# ESP12_DEV_00.net
KiCad netlist of a schematic drawn in Altium Designer
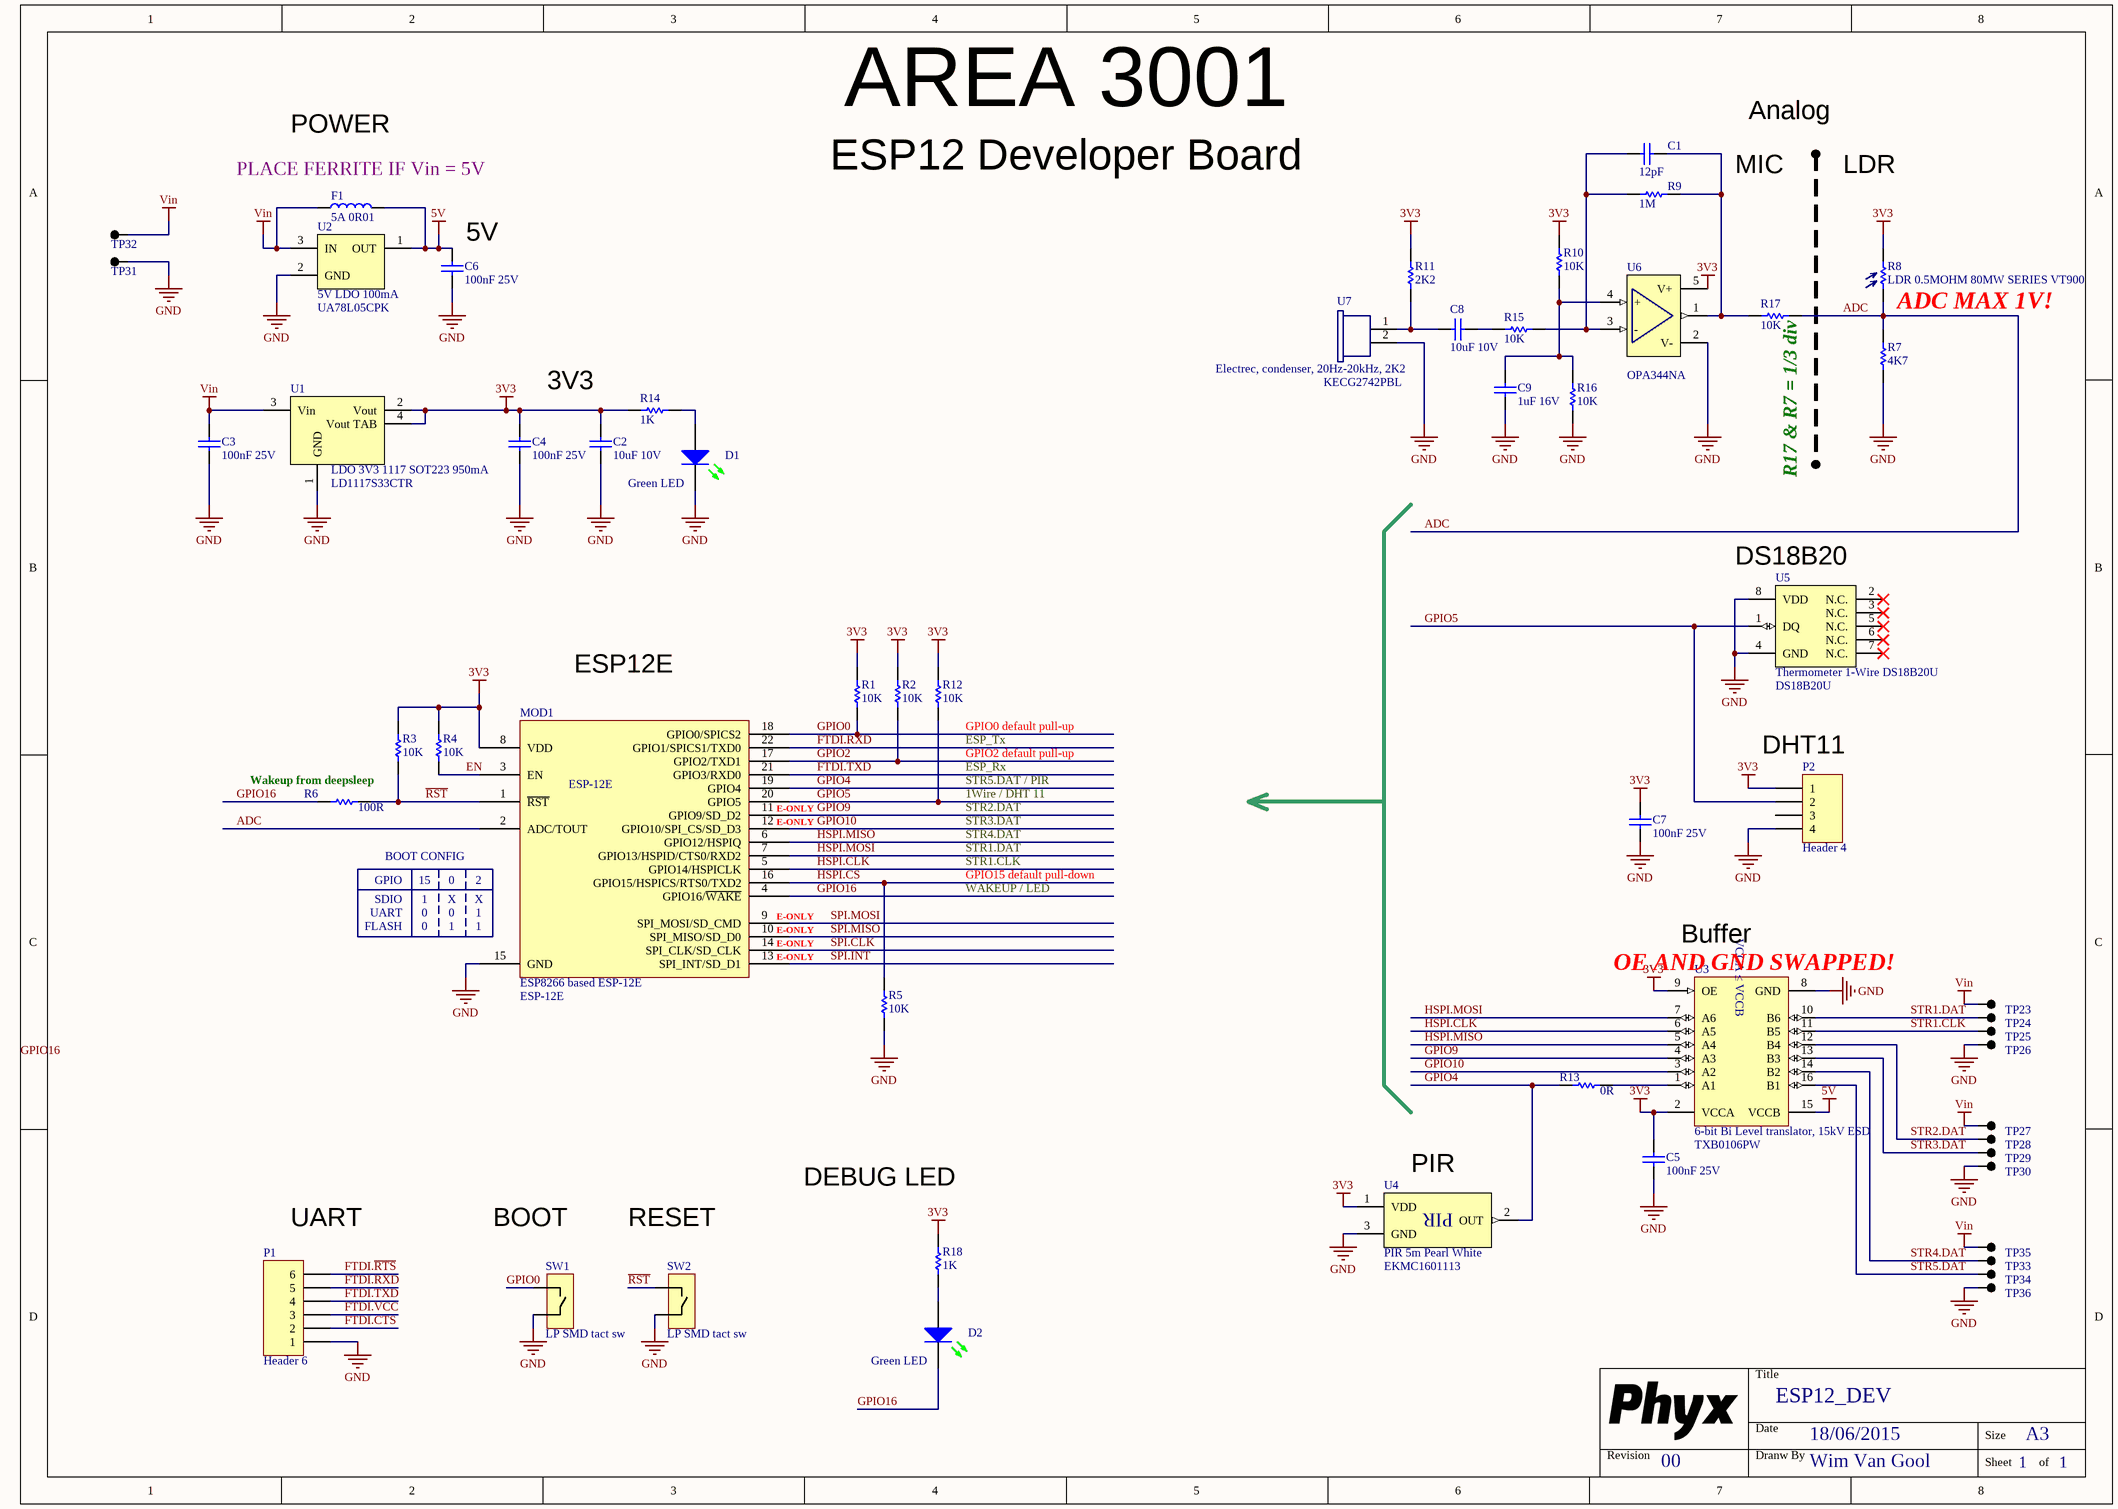
[diagram p0: ESP12_DEV_00.SchDoc]

(export (version "E")
  (design (tool "Eeschema 10.0.6"))
  (components
    (comp (ref "C1")
      (value "12pF")
      (footprint "C0603")
      (description "Capacitor Ceramic")
      (fields (field (name "Comment") "CAP_CERAMIC"))
      (libsource (lib "Phyx_Components") (part "CAP_CERAMIC"))
    )
    (comp (ref "C2")
      (value "10uF 10V")
      (footprint "C0805")
      (description "Capacitor Ceramic")
      (fields (field (name "Comment") "CAP_CERAMIC"))
      (libsource (lib "Phyx_Components") (part "CAP_CERAMIC"))
    )
    (comp (ref "C3")
      (value "100nF 25V")
      (footprint "C0805")
      (description "Capacitor Ceramic")
      (fields (field (name "Comment") "CAP_CERAMIC"))
      (libsource (lib "Phyx_Components") (part "CAP_CERAMIC"))
    )
    (comp (ref "C4")
      (value "100nF 25V")
      (footprint "C0805")
      (description "Capacitor Ceramic")
      (fields (field (name "Comment") "CAP_CERAMIC"))
      (libsource (lib "Phyx_Components") (part "CAP_CERAMIC"))
    )
    (comp (ref "C5")
      (value "100nF 25V")
      (footprint "C0805")
      (description "Capacitor Ceramic")
      (fields (field (name "Comment") "CAP_CERAMIC"))
      (libsource (lib "Phyx_Components") (part "CAP_CERAMIC"))
    )
    (comp (ref "C6")
      (value "100nF 25V")
      (footprint "C0805")
      (description "Capacitor Ceramic")
      (fields (field (name "Comment") "CAP_CERAMIC"))
      (libsource (lib "Phyx_Components") (part "CAP_CERAMIC"))
    )
    (comp (ref "C7")
      (value "100nF 25V")
      (footprint "C0805")
      (description "Capacitor Ceramic")
      (fields (field (name "Comment") "CAP_CERAMIC"))
      (libsource (lib "Phyx_Components") (part "CAP_CERAMIC"))
    )
    (comp (ref "C8")
      (value "10uF 10V")
      (footprint "C0805")
      (description "Capacitor Ceramic")
      (fields (field (name "Comment") "CAP_CERAMIC"))
      (libsource (lib "Phyx_Components") (part "CAP_CERAMIC"))
    )
    (comp (ref "C9")
      (value "1uF 16V")
      (footprint "C0603")
      (description "Capacitor Ceramic")
      (fields (field (name "Comment") "CAP_CERAMIC"))
      (libsource (lib "Phyx_Components") (part "CAP_CERAMIC"))
    )
    (comp (ref "D1")
      (value "Green LED")
      (footprint "LED_0805_GR")
      (description "=Description")
      (libsource (lib "Phyx_Components") (part "LED_GREEN"))
    )
    (comp (ref "D2")
      (value "Green LED")
      (footprint "LED_0805_GR")
      (description "=Description")
      (libsource (lib "Phyx_Components") (part "LED_GREEN"))
    )
    (comp (ref "F1")
      (value "5A 0R01")
      (footprint "L0805")
      (fields (field (name "Comment") "FERRITE"))
      (libsource (lib "Phyx_Components") (part "FERRITE"))
    )
    (comp (ref "MOD1")
      (value "ESP8266 based ESP-12E")
      (footprint "ESP-12E")
      (description "=Description")
      (fields (field (name "ALTIUM_VALUE") "ESP-12E"))
      (libsource (lib "Phyx_Components") (part "ESP-12E"))
    )
    (comp (ref "P1")
      (value "Header 6")
      (footprint "HDR1X6")
      (libsource (lib "Phyx_Components") (part "Header 6"))
    )
    (comp (ref "P2")
      (value "Header 4")
      (footprint "HDR1X4")
      (libsource (lib "Phyx_Components") (part "Header 4"))
    )
    (comp (ref "R1")
      (value "10K")
      (footprint "R0603")
      (fields (field (name "Comment") "RESISTOR"))
      (libsource (lib "Phyx_Components") (part "RESISTOR"))
    )
    (comp (ref "R2")
      (value "10K")
      (footprint "R0603")
      (fields (field (name "Comment") "RESISTOR"))
      (libsource (lib "Phyx_Components") (part "RESISTOR"))
    )
    (comp (ref "R3")
      (value "10K")
      (footprint "R0603")
      (fields (field (name "Comment") "RESISTOR"))
      (libsource (lib "Phyx_Components") (part "RESISTOR"))
    )
    (comp (ref "R4")
      (value "10K")
      (footprint "R0603")
      (fields (field (name "Comment") "RESISTOR"))
      (libsource (lib "Phyx_Components") (part "RESISTOR"))
    )
    (comp (ref "R5")
      (value "10K")
      (footprint "R0603")
      (fields (field (name "Comment") "RESISTOR"))
      (libsource (lib "Phyx_Components") (part "RESISTOR"))
    )
    (comp (ref "R6")
      (value "100R")
      (footprint "R0603")
      (fields (field (name "Comment") "RESISTOR"))
      (libsource (lib "Phyx_Components") (part "RESISTOR"))
    )
    (comp (ref "R7")
      (value "4K7")
      (footprint "R0603")
      (fields (field (name "Comment") "RESISTOR"))
      (libsource (lib "Phyx_Components") (part "RESISTOR"))
    )
    (comp (ref "R8")
      (value "LDR 0.5MOHM 80MW SERIES VT900")
      (footprint "VT900")
      (description "=Description")
      (libsource (lib "Phyx_Components") (part "LDR_2"))
    )
    (comp (ref "R9")
      (value "1M")
      (footprint "R0603")
      (fields (field (name "Comment") "RESISTOR"))
      (libsource (lib "Phyx_Components") (part "RESISTOR"))
    )
    (comp (ref "R10")
      (value "10K")
      (footprint "R0603")
      (fields (field (name "Comment") "RESISTOR"))
      (libsource (lib "Phyx_Components") (part "RESISTOR"))
    )
    (comp (ref "R11")
      (value "2K2")
      (footprint "R0603")
      (fields (field (name "Comment") "RESISTOR"))
      (libsource (lib "Phyx_Components") (part "RESISTOR"))
    )
    (comp (ref "R12")
      (value "10K")
      (footprint "R0603")
      (fields (field (name "Comment") "RESISTOR"))
      (libsource (lib "Phyx_Components") (part "RESISTOR"))
    )
    (comp (ref "R13")
      (value "0R")
      (footprint "R0603")
      (fields (field (name "Comment") "RESISTOR"))
      (libsource (lib "Phyx_Components") (part "RESISTOR"))
    )
    (comp (ref "R14")
      (value "1K")
      (footprint "R0603")
      (fields (field (name "Comment") "RESISTOR"))
      (libsource (lib "Phyx_Components") (part "RESISTOR"))
    )
    (comp (ref "R15")
      (value "10K")
      (footprint "R0603")
      (fields (field (name "Comment") "RESISTOR"))
      (libsource (lib "Phyx_Components") (part "RESISTOR"))
    )
    (comp (ref "R16")
      (value "10K")
      (footprint "R0603")
      (fields (field (name "Comment") "RESISTOR"))
      (libsource (lib "Phyx_Components") (part "RESISTOR"))
    )
    (comp (ref "R17")
      (value "10K")
      (footprint "R0603")
      (fields (field (name "Comment") "RESISTOR"))
      (libsource (lib "Phyx_Components") (part "RESISTOR"))
    )
    (comp (ref "R18")
      (value "1K")
      (footprint "R0603")
      (fields (field (name "Comment") "RESISTOR"))
      (libsource (lib "Phyx_Components") (part "RESISTOR"))
    )
    (comp (ref "SW1")
      (value "LP SMD tact sw")
      (footprint "CK_KMR4")
      (libsource (lib "Phyx_Components") (part "SW_TACT"))
    )
    (comp (ref "SW2")
      (value "LP SMD tact sw")
      (footprint "CK_KMR4")
      (libsource (lib "Phyx_Components") (part "SW_TACT"))
    )
    (comp (ref "TP23")
      (value "TEST_PAD")
      (footprint "TP_2x3mm")
      (libsource (lib "Phyx_Components") (part "TEST_PAD"))
    )
    (comp (ref "TP24")
      (value "TEST_PAD")
      (footprint "TP_2x3mm")
      (libsource (lib "Phyx_Components") (part "TEST_PAD"))
    )
    (comp (ref "TP25")
      (value "TEST_PAD")
      (footprint "TP_2x3mm")
      (libsource (lib "Phyx_Components") (part "TEST_PAD"))
    )
    (comp (ref "TP26")
      (value "TEST_PAD")
      (footprint "TP_2x3mm")
      (libsource (lib "Phyx_Components") (part "TEST_PAD"))
    )
    (comp (ref "TP27")
      (value "TEST_PAD")
      (footprint "TP_2x3mm")
      (libsource (lib "Phyx_Components") (part "TEST_PAD"))
    )
    (comp (ref "TP28")
      (value "TEST_PAD")
      (footprint "TP_2x3mm")
      (libsource (lib "Phyx_Components") (part "TEST_PAD"))
    )
    (comp (ref "TP29")
      (value "TEST_PAD")
      (footprint "TP_2x3mm")
      (libsource (lib "Phyx_Components") (part "TEST_PAD"))
    )
    (comp (ref "TP30")
      (value "TEST_PAD")
      (footprint "TP_2x3mm")
      (libsource (lib "Phyx_Components") (part "TEST_PAD"))
    )
    (comp (ref "TP31")
      (value "TEST_PAD")
      (footprint "TP_2x3mm")
      (libsource (lib "Phyx_Components") (part "TEST_PAD"))
    )
    (comp (ref "TP32")
      (value "TEST_PAD")
      (footprint "TP_2x3mm")
      (libsource (lib "Phyx_Components") (part "TEST_PAD"))
    )
    (comp (ref "TP33")
      (value "TEST_PAD")
      (footprint "TP_2x3mm")
      (libsource (lib "Phyx_Components") (part "TEST_PAD"))
    )
    (comp (ref "TP34")
      (value "TEST_PAD")
      (footprint "TP_2x3mm")
      (libsource (lib "Phyx_Components") (part "TEST_PAD"))
    )
    (comp (ref "TP35")
      (value "TEST_PAD")
      (footprint "TP_2x3mm")
      (libsource (lib "Phyx_Components") (part "TEST_PAD"))
    )
    (comp (ref "TP36")
      (value "TEST_PAD")
      (footprint "TP_2x3mm")
      (libsource (lib "Phyx_Components") (part "TEST_PAD"))
    )
    (comp (ref "U1")
      (value "LDO 3V3 1117 SOT223 950mA")
      (footprint "SOT223")
      (description "=Designator")
      (fields (field (name "ALTIUM_VALUE") "LD1117S33CTR"))
      (libsource (lib "Phyx_Components") (part "LDO_1117_SOT223"))
    )
    (comp (ref "U2")
      (value "5V LDO 100mA")
      (footprint "TI_PK")
      (description "LDO 5V 100mA")
      (fields (field (name "ALTIUM_VALUE") "UA78L05CPK"))
      (libsource (lib "Phyx_Components") (part "UA78L05CPK"))
    )
    (comp (ref "U3")
      (value "6-bit Bi Level translator, 15kV ESD")
      (footprint "TI_PW_R-PDSO-G16")
      (description "=Description")
      (fields (field (name "ALTIUM_VALUE") "TXB0106PW"))
      (libsource (lib "Phyx_Components") (part "TXB0106PW"))
    )
    (comp (ref "U4")
      (value "PIR 5m Pearl White")
      (footprint "PAN_EKMC1601113")
      (description "=Description")
      (fields (field (name "ALTIUM_VALUE") "EKMC1601113"))
      (libsource (lib "Phyx_Components") (part "EKMC160x111x"))
    )
    (comp (ref "U5")
      (value "Thermometer 1-Wire DS18B20U")
      (footprint "MAX_uSOP8")
      (description "=Description")
      (fields (field (name "ALTIUM_VALUE") "DS18B20U"))
      (libsource (lib "Phyx_Components") (part "DS18B20U"))
    )
    (comp (ref "U6")
      (value "OPA344NA")
      (footprint "TI_DBV_R-PDSO-G5")
      (description "=Description")
      (fields (field (name "Comment") "Low Power, Single supply, Rail-to-Rail opamp"))
      (libsource (lib "Phyx_Components") (part "OPA34xNA"))
    )
    (comp (ref "U7")
      (value "Electrec, condenser, 20Hz-20kHz, 2K2")
      (footprint "MIC_2742PB")
      (description "=Description")
      (fields (field (name "ALTIUM_VALUE") "KECG2742PBL"))
      (libsource (lib "Phyx_Components") (part "MIC_ELEC_2"))
    )
  )
  (nets
    (net (code "1") (name "/ADC") (class "Default")
      (node (ref "MOD1") (pin "2") (pinfunction "ADC/TOUT_2") (pintype "passive"))
      (node (ref "R17") (pin "1") (pinfunction "1_1") (pintype "passive"))
      (node (ref "R7") (pin "1") (pinfunction "1_1") (pintype "passive"))
      (node (ref "R8") (pin "2") (pinfunction "2_2") (pintype "passive"))
    )
    (net (code "2") (name "/EN") (class "Default")
      (node (ref "MOD1") (pin "3") (pinfunction "EN_3") (pintype "passive"))
      (node (ref "R4") (pin "2") (pinfunction "2_2") (pintype "passive"))
    )
    (net (code "3") (name "/FTDI.RXD") (class "Default")
      (node (ref "MOD1") (pin "22") (pinfunction "GPIO1/SPICS1/TXD0_22") (pintype "passive"))
      (node (ref "P1") (pin "5") (pinfunction "5_5") (pintype "passive"))
    )
    (net (code "4") (name "/FTDI.TXD") (class "Default")
      (node (ref "MOD1") (pin "21") (pinfunction "GPIO3/RXD0_21") (pintype "passive"))
      (node (ref "P1") (pin "4") (pinfunction "4_4") (pintype "passive"))
    )
    (net (code "5") (name "/FTDI.VCC") (class "Default")
      (node (ref "P1") (pin "3") (pinfunction "3_3") (pintype "passive"))
    )
    (net (code "6") (name "/FTDI.~{CTS}") (class "Default")
      (node (ref "P1") (pin "2") (pinfunction "2_2") (pintype "passive"))
    )
    (net (code "7") (name "/FTDI.~{RTS}") (class "Default")
      (node (ref "P1") (pin "6") (pinfunction "6_6") (pintype "passive"))
    )
    (net (code "8") (name "/GPIO0") (class "Default")
      (node (ref "MOD1") (pin "18") (pinfunction "GPIO0/SPICS2_18") (pintype "passive"))
      (node (ref "R1") (pin "2") (pinfunction "2_2") (pintype "passive"))
      (node (ref "SW1") (pin "1") (pinfunction "1_1") (pintype "passive"))
    )
    (net (code "9") (name "/GPIO2") (class "Default")
      (node (ref "MOD1") (pin "17") (pinfunction "GPIO2/TXD1_17") (pintype "passive"))
      (node (ref "R2") (pin "2") (pinfunction "2_2") (pintype "passive"))
    )
    (net (code "10") (name "/GPIO4") (class "Default")
      (node (ref "MOD1") (pin "19") (pinfunction "GPIO4_19") (pintype "passive"))
      (node (ref "R13") (pin "2") (pinfunction "2_2") (pintype "passive"))
      (node (ref "U4") (pin "2") (pinfunction "OUT_2") (pintype "output"))
    )
    (net (code "11") (name "/GPIO5") (class "Default")
      (node (ref "MOD1") (pin "20") (pinfunction "GPIO5_20") (pintype "passive"))
      (node (ref "P2") (pin "2") (pinfunction "2_2") (pintype "passive"))
      (node (ref "R12") (pin "2") (pinfunction "2_2") (pintype "passive"))
      (node (ref "U5") (pin "1") (pinfunction "DQ_1") (pintype "bidirectional"))
    )
    (net (code "12") (name "/GPIO9") (class "Default")
      (node (ref "MOD1") (pin "11") (pinfunction "GPIO9/SD_D2_11") (pintype "passive"))
      (node (ref "U3") (pin "4") (pinfunction "A3_4") (pintype "bidirectional"))
    )
    (net (code "13") (name "/GPIO10") (class "Default")
      (node (ref "MOD1") (pin "12") (pinfunction "GPIO10/SPI_CS/SD_D3_12") (pintype "passive"))
      (node (ref "U3") (pin "3") (pinfunction "A2_3") (pintype "bidirectional"))
    )
    (net (code "14") (name "/GPIO16") (class "Default")
      (node (ref "D2") (pin "2") (pinfunction "K_2") (pintype "passive"))
      (node (ref "MOD1") (pin "4") (pinfunction "GPIO16/~{WAKE}_4") (pintype "passive"))
      (node (ref "R6") (pin "2") (pinfunction "2_2") (pintype "passive"))
    )
    (net (code "15") (name "/HSPI.CLK") (class "Default")
      (node (ref "MOD1") (pin "5") (pinfunction "GPIO14/HSPICLK_5") (pintype "passive"))
      (node (ref "U3") (pin "6") (pinfunction "A5_6") (pintype "bidirectional"))
    )
    (net (code "16") (name "/HSPI.CS") (class "Default")
      (node (ref "MOD1") (pin "16") (pinfunction "GPIO15/HSPICS/RTS0/TXD2_16") (pintype "passive"))
      (node (ref "R5") (pin "1") (pinfunction "1_1") (pintype "passive"))
    )
    (net (code "17") (name "/HSPI.MISO") (class "Default")
      (node (ref "MOD1") (pin "6") (pinfunction "GPIO12/HSPIQ_6") (pintype "passive"))
      (node (ref "U3") (pin "5") (pinfunction "A4_5") (pintype "bidirectional"))
    )
    (net (code "18") (name "/HSPI.MOSI") (class "Default")
      (node (ref "MOD1") (pin "7") (pinfunction "GPIO13/HSPID/CTS0/RXD2_7") (pintype "passive"))
      (node (ref "U3") (pin "7") (pinfunction "A6_7") (pintype "bidirectional"))
    )
    (net (code "19") (name "/SPI.CLK") (class "Default")
      (node (ref "MOD1") (pin "14") (pinfunction "SPI_CLK/SD_CLK_14") (pintype "passive"))
    )
    (net (code "20") (name "/SPI.INT") (class "Default")
      (node (ref "MOD1") (pin "13") (pinfunction "SPI_INT/SD_D1_13") (pintype "passive"))
    )
    (net (code "21") (name "/SPI.MISO") (class "Default")
      (node (ref "MOD1") (pin "10") (pinfunction "SPI_MISO/SD_D0_10") (pintype "passive"))
    )
    (net (code "22") (name "/SPI.MOSI") (class "Default")
      (node (ref "MOD1") (pin "9") (pinfunction "SPI_MOSI/SD_CMD_9") (pintype "passive"))
    )
    (net (code "23") (name "/STR1.CLK") (class "Default")
      (node (ref "TP25") (pin "1") (pinfunction "1_1") (pintype "passive"))
      (node (ref "U3") (pin "11") (pinfunction "B5_11") (pintype "bidirectional"))
    )
    (net (code "24") (name "/STR1.DAT") (class "Default")
      (node (ref "TP24") (pin "1") (pinfunction "1_1") (pintype "passive"))
      (node (ref "U3") (pin "10") (pinfunction "B6_10") (pintype "bidirectional"))
    )
    (net (code "25") (name "/STR2.DAT") (class "Default")
      (node (ref "TP28") (pin "1") (pinfunction "1_1") (pintype "passive"))
      (node (ref "U3") (pin "12") (pinfunction "B4_12") (pintype "bidirectional"))
    )
    (net (code "26") (name "/STR3.DAT") (class "Default")
      (node (ref "TP29") (pin "1") (pinfunction "1_1") (pintype "passive"))
      (node (ref "U3") (pin "13") (pinfunction "B3_13") (pintype "bidirectional"))
    )
    (net (code "27") (name "/STR4.DAT") (class "Default")
      (node (ref "TP33") (pin "1") (pinfunction "1_1") (pintype "passive"))
      (node (ref "U3") (pin "14") (pinfunction "B2_14") (pintype "bidirectional"))
    )
    (net (code "28") (name "/STR5.DAT") (class "Default")
      (node (ref "TP34") (pin "1") (pinfunction "1_1") (pintype "passive"))
      (node (ref "U3") (pin "16") (pinfunction "B1_16") (pintype "bidirectional"))
    )
    (net (code "29") (name "/~{RST}") (class "Default")
      (node (ref "MOD1") (pin "1") (pinfunction "~{RST}_1") (pintype "passive"))
      (node (ref "R3") (pin "2") (pinfunction "2_2") (pintype "passive"))
      (node (ref "R6") (pin "1") (pinfunction "1_1") (pintype "passive"))
      (node (ref "SW2") (pin "1") (pinfunction "1_1") (pintype "passive"))
    )
    (net (code "30") (name "3V3") (class "Default")
      (node (ref "C2") (pin "1") (pinfunction "1_1") (pintype "passive"))
      (node (ref "C4") (pin "1") (pinfunction "1_1") (pintype "passive"))
      (node (ref "C5") (pin "1") (pinfunction "1_1") (pintype "passive"))
      (node (ref "C7") (pin "1") (pinfunction "1_1") (pintype "passive"))
      (node (ref "MOD1") (pin "8") (pinfunction "VDD_8") (pintype "passive"))
      (node (ref "P2") (pin "1") (pinfunction "1_1") (pintype "passive"))
      (node (ref "R1") (pin "1") (pinfunction "1_1") (pintype "passive"))
      (node (ref "R10") (pin "2") (pinfunction "2_2") (pintype "passive"))
      (node (ref "R11") (pin "1") (pinfunction "1_1") (pintype "passive"))
      (node (ref "R12") (pin "1") (pinfunction "1_1") (pintype "passive"))
      (node (ref "R14") (pin "1") (pinfunction "1_1") (pintype "passive"))
      (node (ref "R18") (pin "1") (pinfunction "1_1") (pintype "passive"))
      (node (ref "R2") (pin "1") (pinfunction "1_1") (pintype "passive"))
      (node (ref "R3") (pin "1") (pinfunction "1_1") (pintype "passive"))
      (node (ref "R4") (pin "1") (pinfunction "1_1") (pintype "passive"))
      (node (ref "R8") (pin "1") (pinfunction "1_1") (pintype "passive"))
      (node (ref "U1") (pin "2") (pinfunction "Vout_2") (pintype "passive"))
      (node (ref "U1") (pin "4") (pinfunction "Vout_TAB_4") (pintype "passive"))
      (node (ref "U3") (pin "2") (pinfunction "VCCA_2") (pintype "power_in"))
      (node (ref "U3") (pin "9") (pinfunction "OE_9") (pintype "input"))
      (node (ref "U4") (pin "1") (pinfunction "VDD_1") (pintype "power_in"))
      (node (ref "U6") (pin "5") (pinfunction "V+_5") (pintype "power_in"))
    )
    (net (code "31") (name "5V") (class "Default")
      (node (ref "C6") (pin "1") (pinfunction "1_1") (pintype "passive"))
      (node (ref "F1") (pin "2") (pinfunction "2_2") (pintype "passive"))
      (node (ref "U2") (pin "1") (pinfunction "OUT_1") (pintype "passive"))
      (node (ref "U3") (pin "15") (pinfunction "VCCB_15") (pintype "power_in"))
    )
    (net (code "32") (name "GND") (class "Default")
      (node (ref "C2") (pin "2") (pinfunction "2_2") (pintype "passive"))
      (node (ref "C3") (pin "2") (pinfunction "2_2") (pintype "passive"))
      (node (ref "C4") (pin "2") (pinfunction "2_2") (pintype "passive"))
      (node (ref "C5") (pin "2") (pinfunction "2_2") (pintype "passive"))
      (node (ref "C6") (pin "2") (pinfunction "2_2") (pintype "passive"))
      (node (ref "C7") (pin "2") (pinfunction "2_2") (pintype "passive"))
      (node (ref "C9") (pin "2") (pinfunction "2_2") (pintype "passive"))
      (node (ref "D1") (pin "2") (pinfunction "K_2") (pintype "passive"))
      (node (ref "MOD1") (pin "15") (pinfunction "GND_15") (pintype "passive"))
      (node (ref "P1") (pin "1") (pinfunction "1_1") (pintype "passive"))
      (node (ref "P2") (pin "4") (pinfunction "4_4") (pintype "passive"))
      (node (ref "R16") (pin "1") (pinfunction "1_1") (pintype "passive"))
      (node (ref "R5") (pin "2") (pinfunction "2_2") (pintype "passive"))
      (node (ref "R7") (pin "2") (pinfunction "2_2") (pintype "passive"))
      (node (ref "SW1") (pin "2") (pinfunction "2_2") (pintype "passive"))
      (node (ref "SW2") (pin "2") (pinfunction "2_2") (pintype "passive"))
      (node (ref "TP26") (pin "1") (pinfunction "1_1") (pintype "passive"))
      (node (ref "TP30") (pin "1") (pinfunction "1_1") (pintype "passive"))
      (node (ref "TP31") (pin "1") (pinfunction "1_1") (pintype "passive"))
      (node (ref "TP36") (pin "1") (pinfunction "1_1") (pintype "passive"))
      (node (ref "U1") (pin "1") (pinfunction "GND_1") (pintype "passive"))
      (node (ref "U2") (pin "2") (pinfunction "GND_2") (pintype "passive"))
      (node (ref "U3") (pin "8") (pinfunction "GND_8") (pintype "power_in"))
      (node (ref "U4") (pin "3") (pinfunction "GND_3") (pintype "power_in"))
      (node (ref "U5") (pin "4") (pinfunction "GND_4") (pintype "power_in"))
      (node (ref "U5") (pin "8") (pinfunction "VDD_8") (pintype "power_in"))
      (node (ref "U6") (pin "2") (pinfunction "V-_2") (pintype "power_in"))
      (node (ref "U7") (pin "2") (pinfunction "2_2") (pintype "passive"))
    )
    (net (code "33") (name "Net-(C8-Pad1)") (class "Default")
      (node (ref "C8") (pin "1") (pinfunction "1_1") (pintype "passive"))
      (node (ref "R15") (pin "2") (pinfunction "2_2") (pintype "passive"))
    )
    (net (code "34") (name "Net-(C8-Pad2)") (class "Default")
      (node (ref "C8") (pin "2") (pinfunction "2_2") (pintype "passive"))
      (node (ref "R11") (pin "2") (pinfunction "2_2") (pintype "passive"))
      (node (ref "U7") (pin "1") (pinfunction "1_1") (pintype "passive"))
    )
    (net (code "35") (name "Net-(D1-A)") (class "Default")
      (node (ref "D1") (pin "1") (pinfunction "A_1") (pintype "passive"))
      (node (ref "R14") (pin "2") (pinfunction "2_2") (pintype "passive"))
    )
    (net (code "36") (name "Net-(D2-A)") (class "Default")
      (node (ref "D2") (pin "1") (pinfunction "A_1") (pintype "passive"))
      (node (ref "R18") (pin "2") (pinfunction "2_2") (pintype "passive"))
    )
    (net (code "37") (name "Net-(U3-A1)") (class "Default")
      (node (ref "R13") (pin "1") (pinfunction "1_1") (pintype "passive"))
      (node (ref "U3") (pin "1") (pinfunction "A1_1") (pintype "bidirectional"))
    )
    (net (code "38") (name "Net-(U6-+)") (class "Default")
      (node (ref "C9") (pin "1") (pinfunction "1_1") (pintype "passive"))
      (node (ref "R10") (pin "1") (pinfunction "1_1") (pintype "passive"))
      (node (ref "R16") (pin "2") (pinfunction "2_2") (pintype "passive"))
      (node (ref "U6") (pin "4") (pinfunction "+_4") (pintype "input"))
    )
    (net (code "39") (name "Net-(U6--)") (class "Default")
      (node (ref "C1") (pin "2") (pinfunction "2_2") (pintype "passive"))
      (node (ref "R15") (pin "1") (pinfunction "1_1") (pintype "passive"))
      (node (ref "R9") (pin "2") (pinfunction "2_2") (pintype "passive"))
      (node (ref "U6") (pin "3") (pinfunction "-_3") (pintype "input"))
    )
    (net (code "40") (name "Net-(U6-OUT)") (class "Default")
      (node (ref "C1") (pin "1") (pinfunction "1_1") (pintype "passive"))
      (node (ref "R17") (pin "2") (pinfunction "2_2") (pintype "passive"))
      (node (ref "R9") (pin "1") (pinfunction "1_1") (pintype "passive"))
      (node (ref "U6") (pin "1") (pinfunction "OUT_1") (pintype "output"))
    )
    (net (code "41") (name "Vin") (class "Default")
      (node (ref "C3") (pin "1") (pinfunction "1_1") (pintype "passive"))
      (node (ref "F1") (pin "1") (pinfunction "1_1") (pintype "passive"))
      (node (ref "TP23") (pin "1") (pinfunction "1_1") (pintype "passive"))
      (node (ref "TP27") (pin "1") (pinfunction "1_1") (pintype "passive"))
      (node (ref "TP32") (pin "1") (pinfunction "1_1") (pintype "passive"))
      (node (ref "TP35") (pin "1") (pinfunction "1_1") (pintype "passive"))
      (node (ref "U1") (pin "3") (pinfunction "Vin_3") (pintype "passive"))
      (node (ref "U2") (pin "3") (pinfunction "IN_3") (pintype "passive"))
    )
    (net (code "42") (name "unconnected-(P2-Pad3)") (class "Default")
      (node (ref "P2") (pin "3") (pinfunction "3_3") (pintype "passive"))
    )
    (net (code "43") (name "unconnected-(U5-N.C.-Pad2)") (class "Default")
      (node (ref "U5") (pin "2") (pinfunction "N.C._2") (pintype "passive+no_connect"))
    )
    (net (code "44") (name "unconnected-(U5-N.C.-Pad3)") (class "Default")
      (node (ref "U5") (pin "3") (pinfunction "N.C._3") (pintype "passive+no_connect"))
    )
    (net (code "45") (name "unconnected-(U5-N.C.-Pad5)") (class "Default")
      (node (ref "U5") (pin "5") (pinfunction "N.C._5") (pintype "passive+no_connect"))
    )
    (net (code "46") (name "unconnected-(U5-N.C.-Pad6)") (class "Default")
      (node (ref "U5") (pin "6") (pinfunction "N.C._6") (pintype "passive+no_connect"))
    )
    (net (code "47") (name "unconnected-(U5-N.C.-Pad7)") (class "Default")
      (node (ref "U5") (pin "7") (pinfunction "N.C._7") (pintype "passive+no_connect"))
    )
  )
)
